# WiFi.net
KiCad netlist of a schematic drawn in Altium Designer
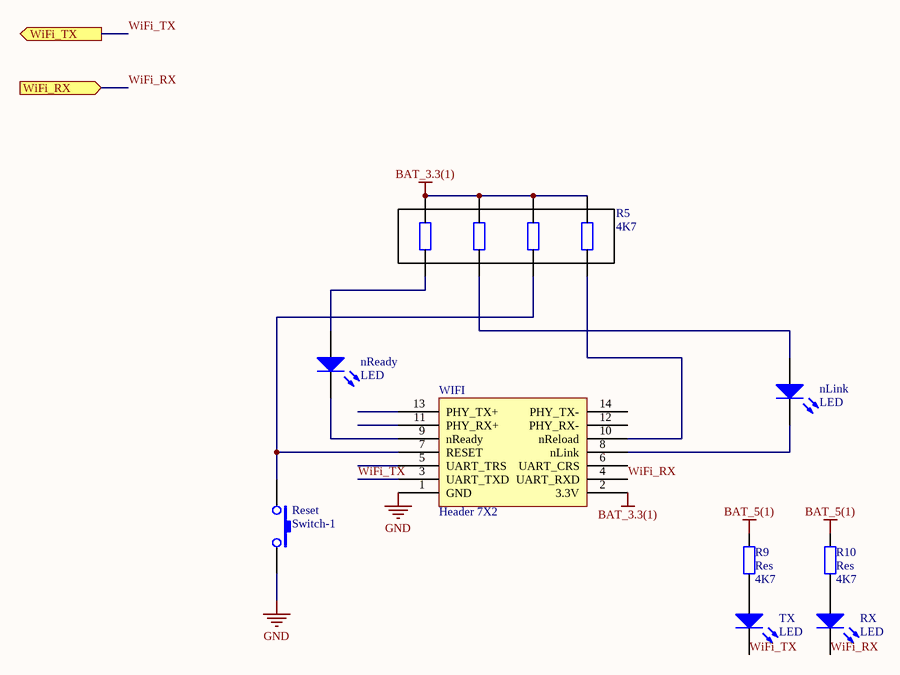
[diagram p0: WiFi.SchDoc]

(export (version "E")
  (design (tool "Eeschema 10.0.6"))
  (components
    (comp (ref "nLink") (value "LED") (footprint "0805 2") (libsource (lib "SmartCarCreative") (part "LED")))
    (comp (ref "nReady") (value "LED") (footprint "0805 2") (libsource (lib "SmartCarCreative") (part "LED")))
    (comp (ref "R5")
      (value "4K7")
      (footprint "8P4R-0603")
      (fields (field (name "Comment") "R x4"))
      (libsource (lib "SmartCarCreative") (part "Res x4"))
    )
    (comp (ref "R9")
      (value "Res")
      (footprint "0805 2")
      (description "Resistor")
      (fields (field (name "ALTIUM_VALUE") "4K7") (field (name "PUBLISHER") "Altium Limited"))
      (libsource (lib "SmartCarCreative") (part "Res"))
    )
    (comp (ref "R10")
      (value "Res")
      (footprint "0805 2")
      (description "Resistor")
      (fields (field (name "ALTIUM_VALUE") "4K7") (field (name "PUBLISHER") "Altium Limited"))
      (libsource (lib "SmartCarCreative") (part "Res"))
    )
    (comp (ref "Reset")
      (value "Switch-1")
      (footprint "轻触按键")
      (libsource (lib "SmartCarCreative") (part "Switch-1"))
    )
    (comp (ref "RX") (value "LED") (footprint "0805 2") (libsource (lib "SmartCarCreative") (part "LED")))
    (comp (ref "TX") (value "LED") (footprint "0805 2") (libsource (lib "SmartCarCreative") (part "LED")))
    (comp (ref "WIFI")
      (value "Header 7X2")
      (footprint "USR-WIFI232-X")
      (libsource (lib "SmartCarCreative") (part "USR-WIFI232-X"))
    )
  )
  (nets
    (net (code "1") (name "/WiFi_RX") (class "Default")
      (node (ref "RX") (pin "2") (pinfunction "K_2") (pintype "passive"))
      (node (ref "WIFI") (pin "4") (pinfunction "UART_RXD_4") (pintype "passive"))
    )
    (net (code "2") (name "/WiFi_TX") (class "Default")
      (node (ref "TX") (pin "2") (pinfunction "K_2") (pintype "passive"))
      (node (ref "WIFI") (pin "3") (pinfunction "UART_TXD_3") (pintype "passive"))
    )
    (net (code "3") (name "BAT_3.3(1)") (class "Default")
      (node (ref "R5") (pin "1") (pinfunction "1_1") (pintype "passive"))
      (node (ref "R5") (pin "3") (pinfunction "3_3") (pintype "passive"))
      (node (ref "R5") (pin "5") (pinfunction "5_5") (pintype "passive"))
      (node (ref "R5") (pin "7") (pinfunction "7_7") (pintype "passive"))
      (node (ref "WIFI") (pin "2") (pinfunction "3.3V_2") (pintype "passive"))
    )
    (net (code "4") (name "BAT_5(1)") (class "Default")
      (node (ref "R10") (pin "2") (pinfunction "2_2") (pintype "passive"))
      (node (ref "R9") (pin "2") (pinfunction "2_2") (pintype "passive"))
    )
    (net (code "5") (name "GND") (class "Default")
      (node (ref "Reset") (pin "2") (pinfunction "2_2") (pintype "passive"))
      (node (ref "WIFI") (pin "1") (pinfunction "GND_1") (pintype "passive"))
    )
    (net (code "6") (name "Net-(RX-A)") (class "Default")
      (node (ref "R10") (pin "1") (pinfunction "1_1") (pintype "passive"))
      (node (ref "RX") (pin "1") (pinfunction "A_1") (pintype "passive"))
    )
    (net (code "7") (name "Net-(TX-A)") (class "Default")
      (node (ref "R9") (pin "1") (pinfunction "1_1") (pintype "passive"))
      (node (ref "TX") (pin "1") (pinfunction "A_1") (pintype "passive"))
    )
    (net (code "8") (name "Net-(WIFI-RESET)") (class "Default")
      (node (ref "R5") (pin "6") (pinfunction "6_6") (pintype "passive"))
      (node (ref "Reset") (pin "1") (pinfunction "1_1") (pintype "passive"))
      (node (ref "WIFI") (pin "7") (pinfunction "RESET_7") (pintype "passive"))
    )
    (net (code "9") (name "Net-(WIFI-nLink)") (class "Default")
      (node (ref "WIFI") (pin "8") (pinfunction "nLink_8") (pintype "passive"))
      (node (ref "nLink") (pin "2") (pinfunction "K_2") (pintype "passive"))
    )
    (net (code "10") (name "Net-(WIFI-nReady)") (class "Default")
      (node (ref "WIFI") (pin "9") (pinfunction "nReady_9") (pintype "passive"))
      (node (ref "nReady") (pin "2") (pinfunction "K_2") (pintype "passive"))
    )
    (net (code "11") (name "Net-(WIFI-nReload)") (class "Default")
      (node (ref "R5") (pin "8") (pinfunction "8_8") (pintype "passive"))
      (node (ref "WIFI") (pin "10") (pinfunction "nReload_10") (pintype "passive"))
    )
    (net (code "12") (name "Net-(nLink-A)") (class "Default")
      (node (ref "R5") (pin "4") (pinfunction "4_4") (pintype "passive"))
      (node (ref "nLink") (pin "1") (pinfunction "A_1") (pintype "passive"))
    )
    (net (code "13") (name "Net-(nReady-A)") (class "Default")
      (node (ref "R5") (pin "2") (pinfunction "2_2") (pintype "passive"))
      (node (ref "nReady") (pin "1") (pinfunction "A_1") (pintype "passive"))
    )
    (net (code "14") (name "unconnected-(WIFI-PHY_RX+-Pad11)") (class "Default")
      (node (ref "WIFI") (pin "11") (pinfunction "PHY_RX+_11") (pintype "passive"))
    )
    (net (code "15") (name "unconnected-(WIFI-PHY_RX--Pad12)") (class "Default")
      (node (ref "WIFI") (pin "12") (pinfunction "PHY_RX-_12") (pintype "passive"))
    )
    (net (code "16") (name "unconnected-(WIFI-PHY_TX+-Pad13)") (class "Default")
      (node (ref "WIFI") (pin "13") (pinfunction "PHY_TX+_13") (pintype "passive"))
    )
    (net (code "17") (name "unconnected-(WIFI-PHY_TX--Pad14)") (class "Default")
      (node (ref "WIFI") (pin "14") (pinfunction "PHY_TX-_14") (pintype "passive"))
    )
    (net (code "18") (name "unconnected-(WIFI-UART_CRS-Pad6)") (class "Default")
      (node (ref "WIFI") (pin "6") (pinfunction "UART_CRS_6") (pintype "passive"))
    )
    (net (code "19") (name "unconnected-(WIFI-UART_TRS-Pad5)") (class "Default")
      (node (ref "WIFI") (pin "5") (pinfunction "UART_TRS_5") (pintype "passive"))
    )
  )
)
